# clock_v0_6.net
KiCad netlist of a schematic drawn in EAGLE
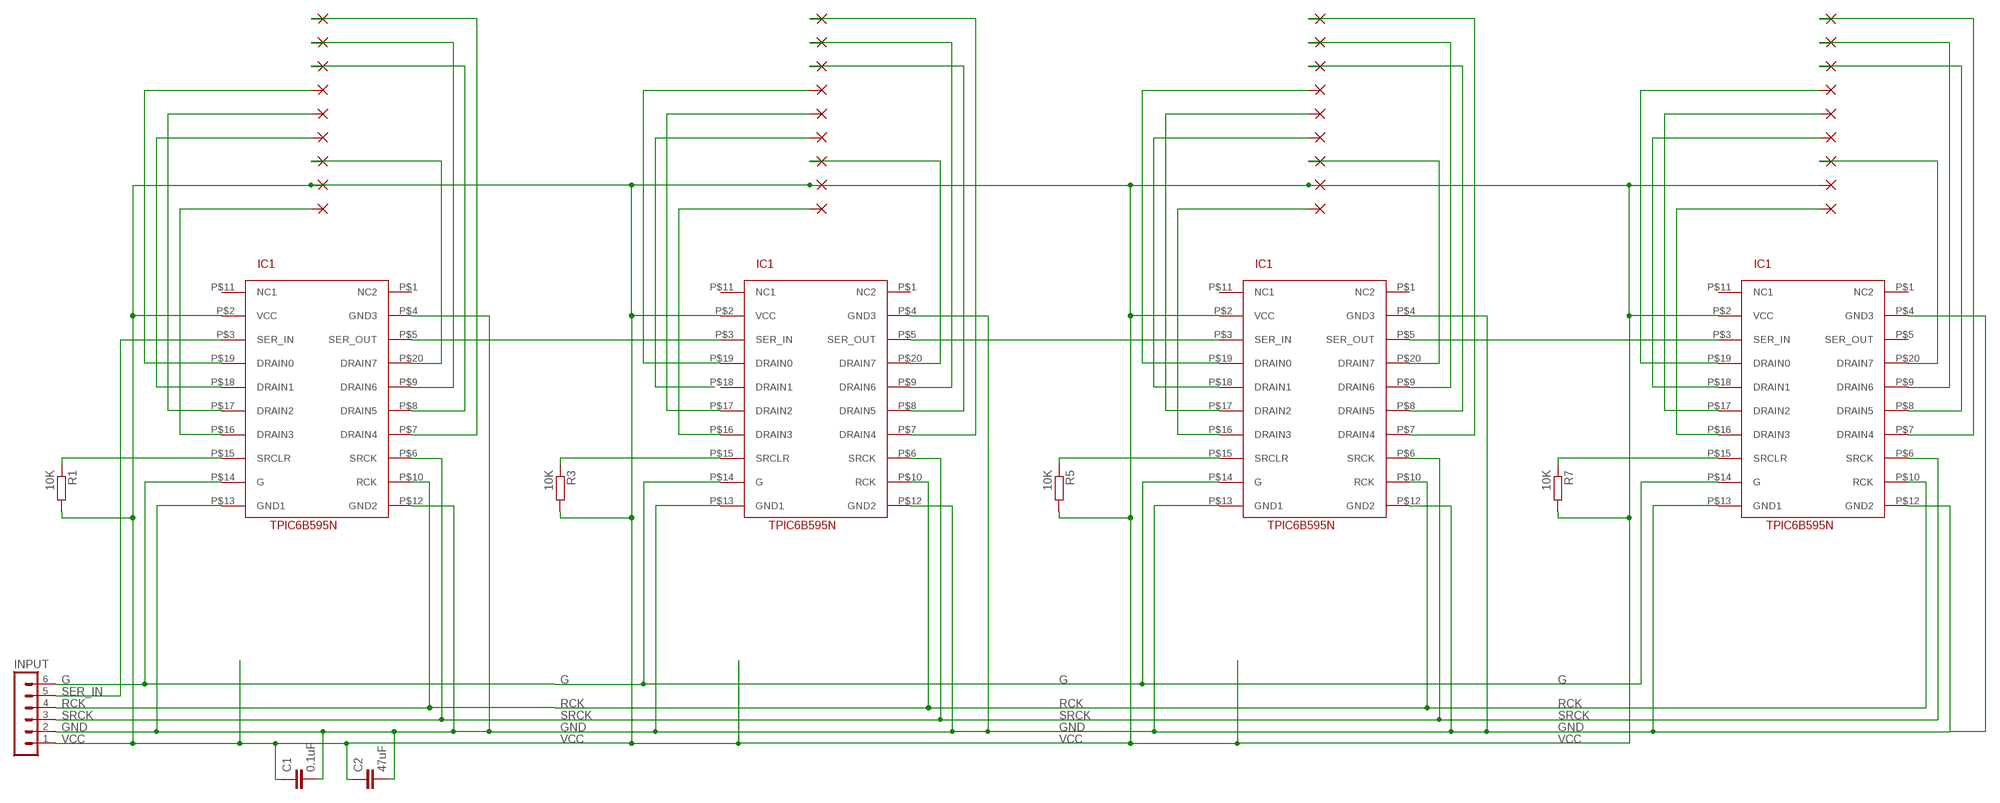
[diagram p0: schematic, sheet 1]

(export (version "E")
  (design (tool "Eeschema 10.0.6"))
  (components
    (comp (ref "C1")
      (value "0.1uF")
      (footprint "eagle-import:RCL_C025-025X050")
      (libsource (lib "eagle-import") (part "RCL_C-EU025-025X050"))
    )
    (comp (ref "C2")
      (value "47uF")
      (footprint "eagle-import:RCL_C025-025X050")
      (libsource (lib "eagle-import") (part "RCL_C-EU025-025X050"))
    )
    (comp (ref "DEC1")
      (value "1,6/0,8")
      (footprint "eagle-import:1,6_0,8")
      (libsource (lib "eagle-import") (part "1,6/0,8"))
    )
    (comp (ref "DEC2")
      (value "1,6/0,8")
      (footprint "eagle-import:1,6_0,8")
      (libsource (lib "eagle-import") (part "1,6/0,8"))
    )
    (comp (ref "DEC4")
      (value "1,6/0,8")
      (footprint "eagle-import:1,6_0,8")
      (libsource (lib "eagle-import") (part "1,6/0,8"))
    )
    (comp (ref "DEC6")
      (value "1,6/0,8")
      (footprint "eagle-import:1,6_0,8")
      (libsource (lib "eagle-import") (part "1,6/0,8"))
    )
    (comp (ref "INPUT")
      (value "CON-LSTB_MA06-1")
      (footprint "eagle-import:CON-LSTB_MA06-1")
      (libsource (lib "eagle-import") (part "CON-LSTB_MA06-1"))
    )
    (comp (ref "R1")
      (value "10K")
      (footprint "eagle-import:RCL_0207_7")
      (libsource (lib "eagle-import") (part "RCL_R-EU_0207/7"))
    )
    (comp (ref "R3")
      (value "10K")
      (footprint "eagle-import:RCL_0207_7")
      (libsource (lib "eagle-import") (part "RCL_R-EU_0207/7"))
    )
    (comp (ref "R5")
      (value "10K")
      (footprint "eagle-import:RCL_0207_7")
      (libsource (lib "eagle-import") (part "RCL_R-EU_0207/7"))
    )
    (comp (ref "R7")
      (value "10K")
      (footprint "eagle-import:RCL_0207_7")
      (libsource (lib "eagle-import") (part "RCL_R-EU_0207/7"))
    )
    (comp (ref "SEGA1")
      (value "1,6/0,8")
      (footprint "eagle-import:1,6_0,8")
      (libsource (lib "eagle-import") (part "1,6/0,8"))
    )
    (comp (ref "SEGA2")
      (value "1,6/0,8")
      (footprint "eagle-import:1,6_0,8")
      (libsource (lib "eagle-import") (part "1,6/0,8"))
    )
    (comp (ref "SEGA4")
      (value "1,6/0,8")
      (footprint "eagle-import:1,6_0,8")
      (libsource (lib "eagle-import") (part "1,6/0,8"))
    )
    (comp (ref "SEGA6")
      (value "1,6/0,8")
      (footprint "eagle-import:1,6_0,8")
      (libsource (lib "eagle-import") (part "1,6/0,8"))
    )
    (comp (ref "SEGB1")
      (value "1,6/0,8")
      (footprint "eagle-import:1,6_0,8")
      (libsource (lib "eagle-import") (part "1,6/0,8"))
    )
    (comp (ref "SEGB2")
      (value "1,6/0,8")
      (footprint "eagle-import:1,6_0,8")
      (libsource (lib "eagle-import") (part "1,6/0,8"))
    )
    (comp (ref "SEGB4")
      (value "1,6/0,8")
      (footprint "eagle-import:1,6_0,8")
      (libsource (lib "eagle-import") (part "1,6/0,8"))
    )
    (comp (ref "SEGB6")
      (value "1,6/0,8")
      (footprint "eagle-import:1,6_0,8")
      (libsource (lib "eagle-import") (part "1,6/0,8"))
    )
    (comp (ref "SEGC1")
      (value "1,6/0,8")
      (footprint "eagle-import:1,6_0,8")
      (libsource (lib "eagle-import") (part "1,6/0,8"))
    )
    (comp (ref "SEGC2")
      (value "1,6/0,8")
      (footprint "eagle-import:1,6_0,8")
      (libsource (lib "eagle-import") (part "1,6/0,8"))
    )
    (comp (ref "SEGC4")
      (value "1,6/0,8")
      (footprint "eagle-import:1,6_0,8")
      (libsource (lib "eagle-import") (part "1,6/0,8"))
    )
    (comp (ref "SEGC6")
      (value "1,6/0,8")
      (footprint "eagle-import:1,6_0,8")
      (libsource (lib "eagle-import") (part "1,6/0,8"))
    )
    (comp (ref "SEGD1")
      (value "1,6/0,8")
      (footprint "eagle-import:1,6_0,8")
      (libsource (lib "eagle-import") (part "1,6/0,8"))
    )
    (comp (ref "SEGD2")
      (value "1,6/0,8")
      (footprint "eagle-import:1,6_0,8")
      (libsource (lib "eagle-import") (part "1,6/0,8"))
    )
    (comp (ref "SEGD4")
      (value "1,6/0,8")
      (footprint "eagle-import:1,6_0,8")
      (libsource (lib "eagle-import") (part "1,6/0,8"))
    )
    (comp (ref "SEGD6")
      (value "1,6/0,8")
      (footprint "eagle-import:1,6_0,8")
      (libsource (lib "eagle-import") (part "1,6/0,8"))
    )
    (comp (ref "SEGE1")
      (value "1,6/0,8")
      (footprint "eagle-import:1,6_0,8")
      (libsource (lib "eagle-import") (part "1,6/0,8"))
    )
    (comp (ref "SEGE2")
      (value "1,6/0,8")
      (footprint "eagle-import:1,6_0,8")
      (libsource (lib "eagle-import") (part "1,6/0,8"))
    )
    (comp (ref "SEGE4")
      (value "1,6/0,8")
      (footprint "eagle-import:1,6_0,8")
      (libsource (lib "eagle-import") (part "1,6/0,8"))
    )
    (comp (ref "SEGE6")
      (value "1,6/0,8")
      (footprint "eagle-import:1,6_0,8")
      (libsource (lib "eagle-import") (part "1,6/0,8"))
    )
    (comp (ref "SEGF1")
      (value "1,6/0,8")
      (footprint "eagle-import:1,6_0,8")
      (libsource (lib "eagle-import") (part "1,6/0,8"))
    )
    (comp (ref "SEGF2")
      (value "1,6/0,8")
      (footprint "eagle-import:1,6_0,8")
      (libsource (lib "eagle-import") (part "1,6/0,8"))
    )
    (comp (ref "SEGF4")
      (value "1,6/0,8")
      (footprint "eagle-import:1,6_0,8")
      (libsource (lib "eagle-import") (part "1,6/0,8"))
    )
    (comp (ref "SEGF6")
      (value "1,6/0,8")
      (footprint "eagle-import:1,6_0,8")
      (libsource (lib "eagle-import") (part "1,6/0,8"))
    )
    (comp (ref "SEGG1")
      (value "1,6/0,8")
      (footprint "eagle-import:1,6_0,8")
      (libsource (lib "eagle-import") (part "1,6/0,8"))
    )
    (comp (ref "SEGG2")
      (value "1,6/0,8")
      (footprint "eagle-import:1,6_0,8")
      (libsource (lib "eagle-import") (part "1,6/0,8"))
    )
    (comp (ref "SEGG4")
      (value "1,6/0,8")
      (footprint "eagle-import:1,6_0,8")
      (libsource (lib "eagle-import") (part "1,6/0,8"))
    )
    (comp (ref "SEGG6")
      (value "1,6/0,8")
      (footprint "eagle-import:1,6_0,8")
      (libsource (lib "eagle-import") (part "1,6/0,8"))
    )
    (comp (ref "U$1")
      (value "TPIC6B595N_TPIC6B595NPDIP-20")
      (footprint "eagle-import:TPIC6B595N_PDIP-20")
      (libsource (lib "eagle-import") (part "TPIC6B595N_TPIC6B595NPDIP-20"))
    )
    (comp (ref "U$3")
      (value "TPIC6B595N_TPIC6B595NPDIP-20")
      (footprint "eagle-import:TPIC6B595N_PDIP-20")
      (libsource (lib "eagle-import") (part "TPIC6B595N_TPIC6B595NPDIP-20"))
    )
    (comp (ref "U$5")
      (value "TPIC6B595N_TPIC6B595NPDIP-20")
      (footprint "eagle-import:TPIC6B595N_PDIP-20")
      (libsource (lib "eagle-import") (part "TPIC6B595N_TPIC6B595NPDIP-20"))
    )
    (comp (ref "U$7")
      (value "TPIC6B595N_TPIC6B595NPDIP-20")
      (footprint "eagle-import:TPIC6B595N_PDIP-20")
      (libsource (lib "eagle-import") (part "TPIC6B595N_TPIC6B595NPDIP-20"))
    )
    (comp (ref "VCC1")
      (value "1,6/0,8")
      (footprint "eagle-import:1,6_0,8")
      (libsource (lib "eagle-import") (part "1,6/0,8"))
    )
    (comp (ref "VCC2")
      (value "1,6/0,8")
      (footprint "eagle-import:1,6_0,8")
      (libsource (lib "eagle-import") (part "1,6/0,8"))
    )
    (comp (ref "VCC4")
      (value "1,6/0,8")
      (footprint "eagle-import:1,6_0,8")
      (libsource (lib "eagle-import") (part "1,6/0,8"))
    )
    (comp (ref "VCC6")
      (value "1,6/0,8")
      (footprint "eagle-import:1,6_0,8")
      (libsource (lib "eagle-import") (part "1,6/0,8"))
    )
  )
  (nets
    (net (code "1") (name "/G") (class "Default")
      (node (ref "INPUT") (pin "6") (pinfunction "6_6") (pintype "passive"))
      (node (ref "U$1") (pin "P$14") (pinfunction "G_P$14") (pintype "bidirectional"))
      (node (ref "U$3") (pin "P$14") (pinfunction "G_P$14") (pintype "bidirectional"))
      (node (ref "U$5") (pin "P$14") (pinfunction "G_P$14") (pintype "bidirectional"))
      (node (ref "U$7") (pin "P$14") (pinfunction "G_P$14") (pintype "bidirectional"))
    )
    (net (code "2") (name "/GND") (class "Default")
      (node (ref "C1") (pin "2") (pinfunction "2_2") (pintype "passive"))
      (node (ref "C2") (pin "2") (pinfunction "2_2") (pintype "passive"))
      (node (ref "INPUT") (pin "2") (pinfunction "2_2") (pintype "passive"))
      (node (ref "U$1") (pin "P$12") (pinfunction "GND2_P$12") (pintype "bidirectional"))
      (node (ref "U$1") (pin "P$13") (pinfunction "GND1_P$13") (pintype "bidirectional"))
      (node (ref "U$1") (pin "P$4") (pinfunction "GND3_P$4") (pintype "bidirectional"))
      (node (ref "U$3") (pin "P$12") (pinfunction "GND2_P$12") (pintype "bidirectional"))
      (node (ref "U$3") (pin "P$13") (pinfunction "GND1_P$13") (pintype "bidirectional"))
      (node (ref "U$3") (pin "P$4") (pinfunction "GND3_P$4") (pintype "bidirectional"))
      (node (ref "U$5") (pin "P$12") (pinfunction "GND2_P$12") (pintype "bidirectional"))
      (node (ref "U$5") (pin "P$13") (pinfunction "GND1_P$13") (pintype "bidirectional"))
      (node (ref "U$5") (pin "P$4") (pinfunction "GND3_P$4") (pintype "bidirectional"))
      (node (ref "U$7") (pin "P$12") (pinfunction "GND2_P$12") (pintype "bidirectional"))
      (node (ref "U$7") (pin "P$13") (pinfunction "GND1_P$13") (pintype "bidirectional"))
      (node (ref "U$7") (pin "P$4") (pinfunction "GND3_P$4") (pintype "bidirectional"))
    )
    (net (code "3") (name "/RCK") (class "Default")
      (node (ref "INPUT") (pin "4") (pinfunction "4_4") (pintype "passive"))
      (node (ref "U$1") (pin "P$10") (pinfunction "RCK_P$10") (pintype "bidirectional"))
      (node (ref "U$3") (pin "P$10") (pinfunction "RCK_P$10") (pintype "bidirectional"))
      (node (ref "U$5") (pin "P$10") (pinfunction "RCK_P$10") (pintype "bidirectional"))
      (node (ref "U$7") (pin "P$10") (pinfunction "RCK_P$10") (pintype "bidirectional"))
    )
    (net (code "4") (name "/SER_IN") (class "Default")
      (node (ref "INPUT") (pin "5") (pinfunction "5_5") (pintype "passive"))
      (node (ref "U$1") (pin "P$3") (pinfunction "SER_IN_P$3") (pintype "bidirectional"))
    )
    (net (code "5") (name "/SRCK") (class "Default")
      (node (ref "INPUT") (pin "3") (pinfunction "3_3") (pintype "passive"))
      (node (ref "U$1") (pin "P$6") (pinfunction "SRCK_P$6") (pintype "bidirectional"))
      (node (ref "U$3") (pin "P$6") (pinfunction "SRCK_P$6") (pintype "bidirectional"))
      (node (ref "U$5") (pin "P$6") (pinfunction "SRCK_P$6") (pintype "bidirectional"))
      (node (ref "U$7") (pin "P$6") (pinfunction "SRCK_P$6") (pintype "bidirectional"))
    )
    (net (code "6") (name "/VCC") (class "Default")
      (node (ref "C1") (pin "1") (pinfunction "1_1") (pintype "passive"))
      (node (ref "C2") (pin "1") (pinfunction "1_1") (pintype "passive"))
      (node (ref "INPUT") (pin "1") (pinfunction "1_1") (pintype "passive"))
      (node (ref "R1") (pin "2") (pinfunction "2_2") (pintype "passive"))
      (node (ref "R3") (pin "2") (pinfunction "2_2") (pintype "passive"))
      (node (ref "R5") (pin "2") (pinfunction "2_2") (pintype "passive"))
      (node (ref "R7") (pin "2") (pinfunction "2_2") (pintype "passive"))
      (node (ref "U$1") (pin "P$2") (pinfunction "VCC_P$2") (pintype "bidirectional"))
      (node (ref "U$3") (pin "P$2") (pinfunction "VCC_P$2") (pintype "bidirectional"))
      (node (ref "U$5") (pin "P$2") (pinfunction "VCC_P$2") (pintype "bidirectional"))
      (node (ref "U$7") (pin "P$2") (pinfunction "VCC_P$2") (pintype "bidirectional"))
      (node (ref "VCC1") (pin "1") (pinfunction "P_1") (pintype "passive"))
      (node (ref "VCC2") (pin "1") (pinfunction "P_1") (pintype "passive"))
      (node (ref "VCC4") (pin "1") (pinfunction "P_1") (pintype "passive"))
      (node (ref "VCC6") (pin "1") (pinfunction "P_1") (pintype "passive"))
    )
    (net (code "7") (name "Net-(DEC1-P)") (class "Default")
      (node (ref "DEC1") (pin "1") (pinfunction "P_1") (pintype "passive"))
      (node (ref "U$1") (pin "P$20") (pinfunction "DRAIN7_P$20") (pintype "bidirectional"))
    )
    (net (code "8") (name "Net-(DEC2-P)") (class "Default")
      (node (ref "DEC2") (pin "1") (pinfunction "P_1") (pintype "passive"))
      (node (ref "U$3") (pin "P$20") (pinfunction "DRAIN7_P$20") (pintype "bidirectional"))
    )
    (net (code "9") (name "Net-(DEC4-P)") (class "Default")
      (node (ref "DEC4") (pin "1") (pinfunction "P_1") (pintype "passive"))
      (node (ref "U$5") (pin "P$20") (pinfunction "DRAIN7_P$20") (pintype "bidirectional"))
    )
    (net (code "10") (name "Net-(DEC6-P)") (class "Default")
      (node (ref "DEC6") (pin "1") (pinfunction "P_1") (pintype "passive"))
      (node (ref "U$7") (pin "P$20") (pinfunction "DRAIN7_P$20") (pintype "bidirectional"))
    )
    (net (code "11") (name "Net-(SEGA1-P)") (class "Default")
      (node (ref "SEGA1") (pin "1") (pinfunction "P_1") (pintype "passive"))
      (node (ref "U$1") (pin "P$19") (pinfunction "DRAIN0_P$19") (pintype "bidirectional"))
    )
    (net (code "12") (name "Net-(SEGA2-P)") (class "Default")
      (node (ref "SEGA2") (pin "1") (pinfunction "P_1") (pintype "passive"))
      (node (ref "U$3") (pin "P$19") (pinfunction "DRAIN0_P$19") (pintype "bidirectional"))
    )
    (net (code "13") (name "Net-(SEGA4-P)") (class "Default")
      (node (ref "SEGA4") (pin "1") (pinfunction "P_1") (pintype "passive"))
      (node (ref "U$5") (pin "P$19") (pinfunction "DRAIN0_P$19") (pintype "bidirectional"))
    )
    (net (code "14") (name "Net-(SEGA6-P)") (class "Default")
      (node (ref "SEGA6") (pin "1") (pinfunction "P_1") (pintype "passive"))
      (node (ref "U$7") (pin "P$19") (pinfunction "DRAIN0_P$19") (pintype "bidirectional"))
    )
    (net (code "15") (name "Net-(SEGB1-P)") (class "Default")
      (node (ref "SEGB1") (pin "1") (pinfunction "P_1") (pintype "passive"))
      (node (ref "U$1") (pin "P$18") (pinfunction "DRAIN1_P$18") (pintype "bidirectional"))
    )
    (net (code "16") (name "Net-(SEGB4-P)") (class "Default")
      (node (ref "SEGB4") (pin "1") (pinfunction "P_1") (pintype "passive"))
      (node (ref "U$5") (pin "P$18") (pinfunction "DRAIN1_P$18") (pintype "bidirectional"))
    )
    (net (code "17") (name "Net-(SEGB6-P)") (class "Default")
      (node (ref "SEGB6") (pin "1") (pinfunction "P_1") (pintype "passive"))
      (node (ref "U$7") (pin "P$18") (pinfunction "DRAIN1_P$18") (pintype "bidirectional"))
    )
    (net (code "18") (name "Net-(SEGC1-P)") (class "Default")
      (node (ref "SEGC1") (pin "1") (pinfunction "P_1") (pintype "passive"))
      (node (ref "U$1") (pin "P$17") (pinfunction "DRAIN2_P$17") (pintype "bidirectional"))
    )
    (net (code "19") (name "Net-(SEGC2-P)") (class "Default")
      (node (ref "SEGC2") (pin "1") (pinfunction "P_1") (pintype "passive"))
      (node (ref "U$3") (pin "P$17") (pinfunction "DRAIN2_P$17") (pintype "bidirectional"))
    )
    (net (code "20") (name "Net-(SEGC4-P)") (class "Default")
      (node (ref "SEGC4") (pin "1") (pinfunction "P_1") (pintype "passive"))
      (node (ref "U$5") (pin "P$17") (pinfunction "DRAIN2_P$17") (pintype "bidirectional"))
    )
    (net (code "21") (name "Net-(SEGC6-P)") (class "Default")
      (node (ref "SEGC6") (pin "1") (pinfunction "P_1") (pintype "passive"))
      (node (ref "U$7") (pin "P$17") (pinfunction "DRAIN2_P$17") (pintype "bidirectional"))
    )
    (net (code "22") (name "Net-(SEGD1-P)") (class "Default")
      (node (ref "SEGD1") (pin "1") (pinfunction "P_1") (pintype "passive"))
      (node (ref "U$1") (pin "P$16") (pinfunction "DRAIN3_P$16") (pintype "bidirectional"))
    )
    (net (code "23") (name "Net-(SEGD2-P)") (class "Default")
      (node (ref "SEGD2") (pin "1") (pinfunction "P_1") (pintype "passive"))
      (node (ref "U$3") (pin "P$16") (pinfunction "DRAIN3_P$16") (pintype "bidirectional"))
    )
    (net (code "24") (name "Net-(SEGD4-P)") (class "Default")
      (node (ref "SEGD4") (pin "1") (pinfunction "P_1") (pintype "passive"))
      (node (ref "U$5") (pin "P$16") (pinfunction "DRAIN3_P$16") (pintype "bidirectional"))
    )
    (net (code "25") (name "Net-(SEGD6-P)") (class "Default")
      (node (ref "SEGD6") (pin "1") (pinfunction "P_1") (pintype "passive"))
      (node (ref "U$7") (pin "P$16") (pinfunction "DRAIN3_P$16") (pintype "bidirectional"))
    )
    (net (code "26") (name "Net-(SEGE1-P)") (class "Default")
      (node (ref "SEGE1") (pin "1") (pinfunction "P_1") (pintype "passive"))
      (node (ref "U$1") (pin "P$7") (pinfunction "DRAIN4_P$7") (pintype "bidirectional"))
    )
    (net (code "27") (name "Net-(SEGE2-P)") (class "Default")
      (node (ref "SEGE2") (pin "1") (pinfunction "P_1") (pintype "passive"))
      (node (ref "U$3") (pin "P$7") (pinfunction "DRAIN4_P$7") (pintype "bidirectional"))
    )
    (net (code "28") (name "Net-(SEGE4-P)") (class "Default")
      (node (ref "SEGE4") (pin "1") (pinfunction "P_1") (pintype "passive"))
      (node (ref "U$5") (pin "P$7") (pinfunction "DRAIN4_P$7") (pintype "bidirectional"))
    )
    (net (code "29") (name "Net-(SEGE6-P)") (class "Default")
      (node (ref "SEGE6") (pin "1") (pinfunction "P_1") (pintype "passive"))
      (node (ref "U$7") (pin "P$7") (pinfunction "DRAIN4_P$7") (pintype "bidirectional"))
    )
    (net (code "30") (name "Net-(SEGF1-P)") (class "Default")
      (node (ref "SEGF1") (pin "1") (pinfunction "P_1") (pintype "passive"))
      (node (ref "U$1") (pin "P$8") (pinfunction "DRAIN5_P$8") (pintype "bidirectional"))
    )
    (net (code "31") (name "Net-(SEGF2-P)") (class "Default")
      (node (ref "SEGF2") (pin "1") (pinfunction "P_1") (pintype "passive"))
      (node (ref "U$3") (pin "P$8") (pinfunction "DRAIN5_P$8") (pintype "bidirectional"))
    )
    (net (code "32") (name "Net-(SEGF4-P)") (class "Default")
      (node (ref "SEGF4") (pin "1") (pinfunction "P_1") (pintype "passive"))
      (node (ref "U$5") (pin "P$8") (pinfunction "DRAIN5_P$8") (pintype "bidirectional"))
    )
    (net (code "33") (name "Net-(SEGF6-P)") (class "Default")
      (node (ref "SEGF6") (pin "1") (pinfunction "P_1") (pintype "passive"))
      (node (ref "U$7") (pin "P$8") (pinfunction "DRAIN5_P$8") (pintype "bidirectional"))
    )
    (net (code "34") (name "Net-(SEGG1-P)") (class "Default")
      (node (ref "SEGG1") (pin "1") (pinfunction "P_1") (pintype "passive"))
      (node (ref "U$1") (pin "P$9") (pinfunction "DRAIN6_P$9") (pintype "bidirectional"))
    )
    (net (code "35") (name "Net-(SEGG2-P)") (class "Default")
      (node (ref "SEGG2") (pin "1") (pinfunction "P_1") (pintype "passive"))
      (node (ref "U$3") (pin "P$9") (pinfunction "DRAIN6_P$9") (pintype "bidirectional"))
    )
    (net (code "36") (name "Net-(SEGG4-P)") (class "Default")
      (node (ref "SEGG4") (pin "1") (pinfunction "P_1") (pintype "passive"))
      (node (ref "U$5") (pin "P$9") (pinfunction "DRAIN6_P$9") (pintype "bidirectional"))
    )
    (net (code "37") (name "Net-(SEGG6-P)") (class "Default")
      (node (ref "SEGG6") (pin "1") (pinfunction "P_1") (pintype "passive"))
      (node (ref "U$7") (pin "P$9") (pinfunction "DRAIN6_P$9") (pintype "bidirectional"))
    )
    (net (code "38") (name "Net-(U$1-SER_OUT)") (class "Default")
      (node (ref "U$1") (pin "P$5") (pinfunction "SER_OUT_P$5") (pintype "bidirectional"))
      (node (ref "U$3") (pin "P$3") (pinfunction "SER_IN_P$3") (pintype "bidirectional"))
    )
    (net (code "39") (name "Net-(U$1-SRCLR)") (class "Default")
      (node (ref "R1") (pin "1") (pinfunction "1_1") (pintype "passive"))
      (node (ref "U$1") (pin "P$15") (pinfunction "SRCLR_P$15") (pintype "bidirectional"))
    )
    (net (code "40") (name "Net-(U$3-SER_OUT)") (class "Default")
      (node (ref "U$3") (pin "P$5") (pinfunction "SER_OUT_P$5") (pintype "bidirectional"))
      (node (ref "U$5") (pin "P$3") (pinfunction "SER_IN_P$3") (pintype "bidirectional"))
    )
    (net (code "41") (name "Net-(U$3-SRCLR)") (class "Default")
      (node (ref "R3") (pin "1") (pinfunction "1_1") (pintype "passive"))
      (node (ref "U$3") (pin "P$15") (pinfunction "SRCLR_P$15") (pintype "bidirectional"))
    )
    (net (code "42") (name "Net-(U$5-SER_OUT)") (class "Default")
      (node (ref "U$5") (pin "P$5") (pinfunction "SER_OUT_P$5") (pintype "bidirectional"))
      (node (ref "U$7") (pin "P$3") (pinfunction "SER_IN_P$3") (pintype "bidirectional"))
    )
    (net (code "43") (name "Net-(U$5-SRCLR)") (class "Default")
      (node (ref "R5") (pin "1") (pinfunction "1_1") (pintype "passive"))
      (node (ref "U$5") (pin "P$15") (pinfunction "SRCLR_P$15") (pintype "bidirectional"))
    )
    (net (code "44") (name "Net-(U$7-SRCLR)") (class "Default")
      (node (ref "R7") (pin "1") (pinfunction "1_1") (pintype "passive"))
      (node (ref "U$7") (pin "P$15") (pinfunction "SRCLR_P$15") (pintype "bidirectional"))
    )
    (net (code "45") (name "unconnected-(SEGB2-P-Pad1)") (class "Default")
      (node (ref "SEGB2") (pin "1") (pinfunction "P_1") (pintype "passive"))
    )
    (net (code "46") (name "unconnected-(U$1-NC1-PadP$11)") (class "Default")
      (node (ref "U$1") (pin "P$11") (pinfunction "NC1_P$11") (pintype "bidirectional"))
    )
    (net (code "47") (name "unconnected-(U$1-NC2-PadP$1)") (class "Default")
      (node (ref "U$1") (pin "P$1") (pinfunction "NC2_P$1") (pintype "bidirectional"))
    )
    (net (code "48") (name "unconnected-(U$3-DRAIN1-PadP$18)") (class "Default")
      (node (ref "U$3") (pin "P$18") (pinfunction "DRAIN1_P$18") (pintype "bidirectional"))
    )
    (net (code "49") (name "unconnected-(U$3-NC1-PadP$11)") (class "Default")
      (node (ref "U$3") (pin "P$11") (pinfunction "NC1_P$11") (pintype "bidirectional"))
    )
    (net (code "50") (name "unconnected-(U$3-NC2-PadP$1)") (class "Default")
      (node (ref "U$3") (pin "P$1") (pinfunction "NC2_P$1") (pintype "bidirectional"))
    )
    (net (code "51") (name "unconnected-(U$5-NC1-PadP$11)") (class "Default")
      (node (ref "U$5") (pin "P$11") (pinfunction "NC1_P$11") (pintype "bidirectional"))
    )
    (net (code "52") (name "unconnected-(U$5-NC2-PadP$1)") (class "Default")
      (node (ref "U$5") (pin "P$1") (pinfunction "NC2_P$1") (pintype "bidirectional"))
    )
    (net (code "53") (name "unconnected-(U$7-NC1-PadP$11)") (class "Default")
      (node (ref "U$7") (pin "P$11") (pinfunction "NC1_P$11") (pintype "bidirectional"))
    )
    (net (code "54") (name "unconnected-(U$7-NC2-PadP$1)") (class "Default")
      (node (ref "U$7") (pin "P$1") (pinfunction "NC2_P$1") (pintype "bidirectional"))
    )
    (net (code "55") (name "unconnected-(U$7-SER_OUT-PadP$5)") (class "Default")
      (node (ref "U$7") (pin "P$5") (pinfunction "SER_OUT_P$5") (pintype "bidirectional"))
    )
  )
)
